# poweruptimer.net
KiCad netlist of a schematic drawn in EAGLE
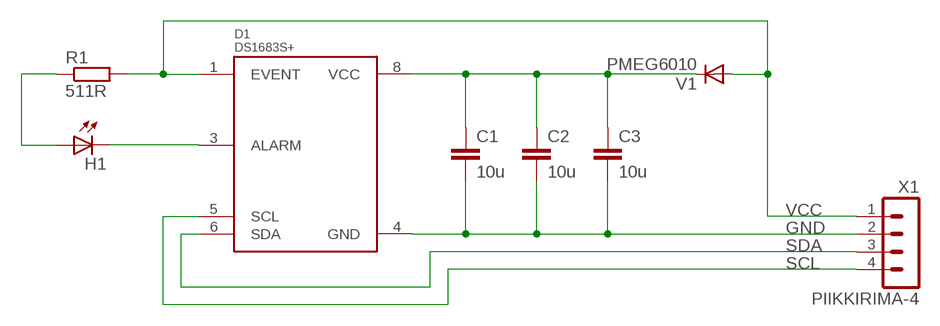
[diagram p0: schematic, sheet 1]

(export (version "E")
  (design (tool "Eeschema 10.0.6"))
  (components
    (comp (ref "C1")
      (value "10u")
      (footprint "eagle-import:C0805")
      (libsource (lib "eagle-import") (part "C-EUC0805"))
    )
    (comp (ref "C2")
      (value "10u")
      (footprint "eagle-import:C0805")
      (libsource (lib "eagle-import") (part "C-EUC0805"))
    )
    (comp (ref "C3")
      (value "10u")
      (footprint "eagle-import:C0805")
      (libsource (lib "eagle-import") (part "C-EUC0805"))
    )
    (comp (ref "D1")
      (value "DS1683S+")
      (footprint "eagle-import:SOIC8-N_MC")
      (libsource (lib "eagle-import") (part "DS1683S+"))
    )
    (comp (ref "H1")
      (value "LEDCHIP-LED0603")
      (footprint "eagle-import:CHIP-LED0603")
      (libsource (lib "eagle-import") (part "LEDCHIP-LED0603"))
    )
    (comp (ref "R1")
      (value "511R")
      (footprint "eagle-import:R0603")
      (libsource (lib "eagle-import") (part "R-EU_R0603"))
    )
    (comp (ref "V1")
      (value "PMEG6010")
      (footprint "eagle-import:SOD323-R")
      (libsource (lib "eagle-import") (part "DIODE-SOD323-R"))
    )
    (comp (ref "X1")
      (value "PIIKKIRIMA-4")
      (footprint "eagle-import:PIIKKIRIMA-4")
      (libsource (lib "eagle-import") (part "PIIKKIRIMA-4"))
    )
  )
  (nets
    (net (code "1") (name "/GND") (class "Default")
      (node (ref "C1") (pin "2") (pinfunction "2_2") (pintype "passive"))
      (node (ref "C2") (pin "2") (pinfunction "2_2") (pintype "passive"))
      (node (ref "C3") (pin "2") (pinfunction "2_2") (pintype "passive"))
      (node (ref "D1") (pin "4") (pinfunction "GND_4") (pintype "bidirectional"))
      (node (ref "X1") (pin "2") (pinfunction "2_2") (pintype "passive"))
    )
    (net (code "2") (name "/SCL") (class "Default")
      (node (ref "D1") (pin "5") (pinfunction "SCL_5") (pintype "bidirectional"))
      (node (ref "X1") (pin "4") (pinfunction "4_4") (pintype "passive"))
    )
    (net (code "3") (name "/SDA") (class "Default")
      (node (ref "D1") (pin "6") (pinfunction "SDA_6") (pintype "bidirectional"))
      (node (ref "X1") (pin "3") (pinfunction "3_3") (pintype "passive"))
    )
    (net (code "4") (name "/VCC") (class "Default")
      (node (ref "D1") (pin "1") (pinfunction "EVENT_1") (pintype "bidirectional"))
      (node (ref "R1") (pin "2") (pinfunction "2_2") (pintype "passive"))
      (node (ref "V1") (pin "A") (pinfunction "A_A") (pintype "passive"))
      (node (ref "X1") (pin "1") (pinfunction "1_1") (pintype "passive"))
    )
    (net (code "5") (name "Net-(D1-ALARM)") (class "Default")
      (node (ref "D1") (pin "3") (pinfunction "ALARM_3") (pintype "bidirectional"))
      (node (ref "H1") (pin "C") (pinfunction "C_C") (pintype "passive"))
    )
    (net (code "6") (name "Net-(D1-VCC)") (class "Default")
      (node (ref "C1") (pin "1") (pinfunction "1_1") (pintype "passive"))
      (node (ref "C2") (pin "1") (pinfunction "1_1") (pintype "passive"))
      (node (ref "C3") (pin "1") (pinfunction "1_1") (pintype "passive"))
      (node (ref "D1") (pin "8") (pinfunction "VCC_8") (pintype "bidirectional"))
      (node (ref "V1") (pin "C") (pinfunction "C_C") (pintype "passive"))
    )
    (net (code "7") (name "Net-(H1-PadA)") (class "Default")
      (node (ref "H1") (pin "A") (pinfunction "A_A") (pintype "passive"))
      (node (ref "R1") (pin "1") (pinfunction "1_1") (pintype "passive"))
    )
  )
)
